# Tasmota_ESP32C6-2.net
KiCad netlist of a schematic drawn in EAGLE
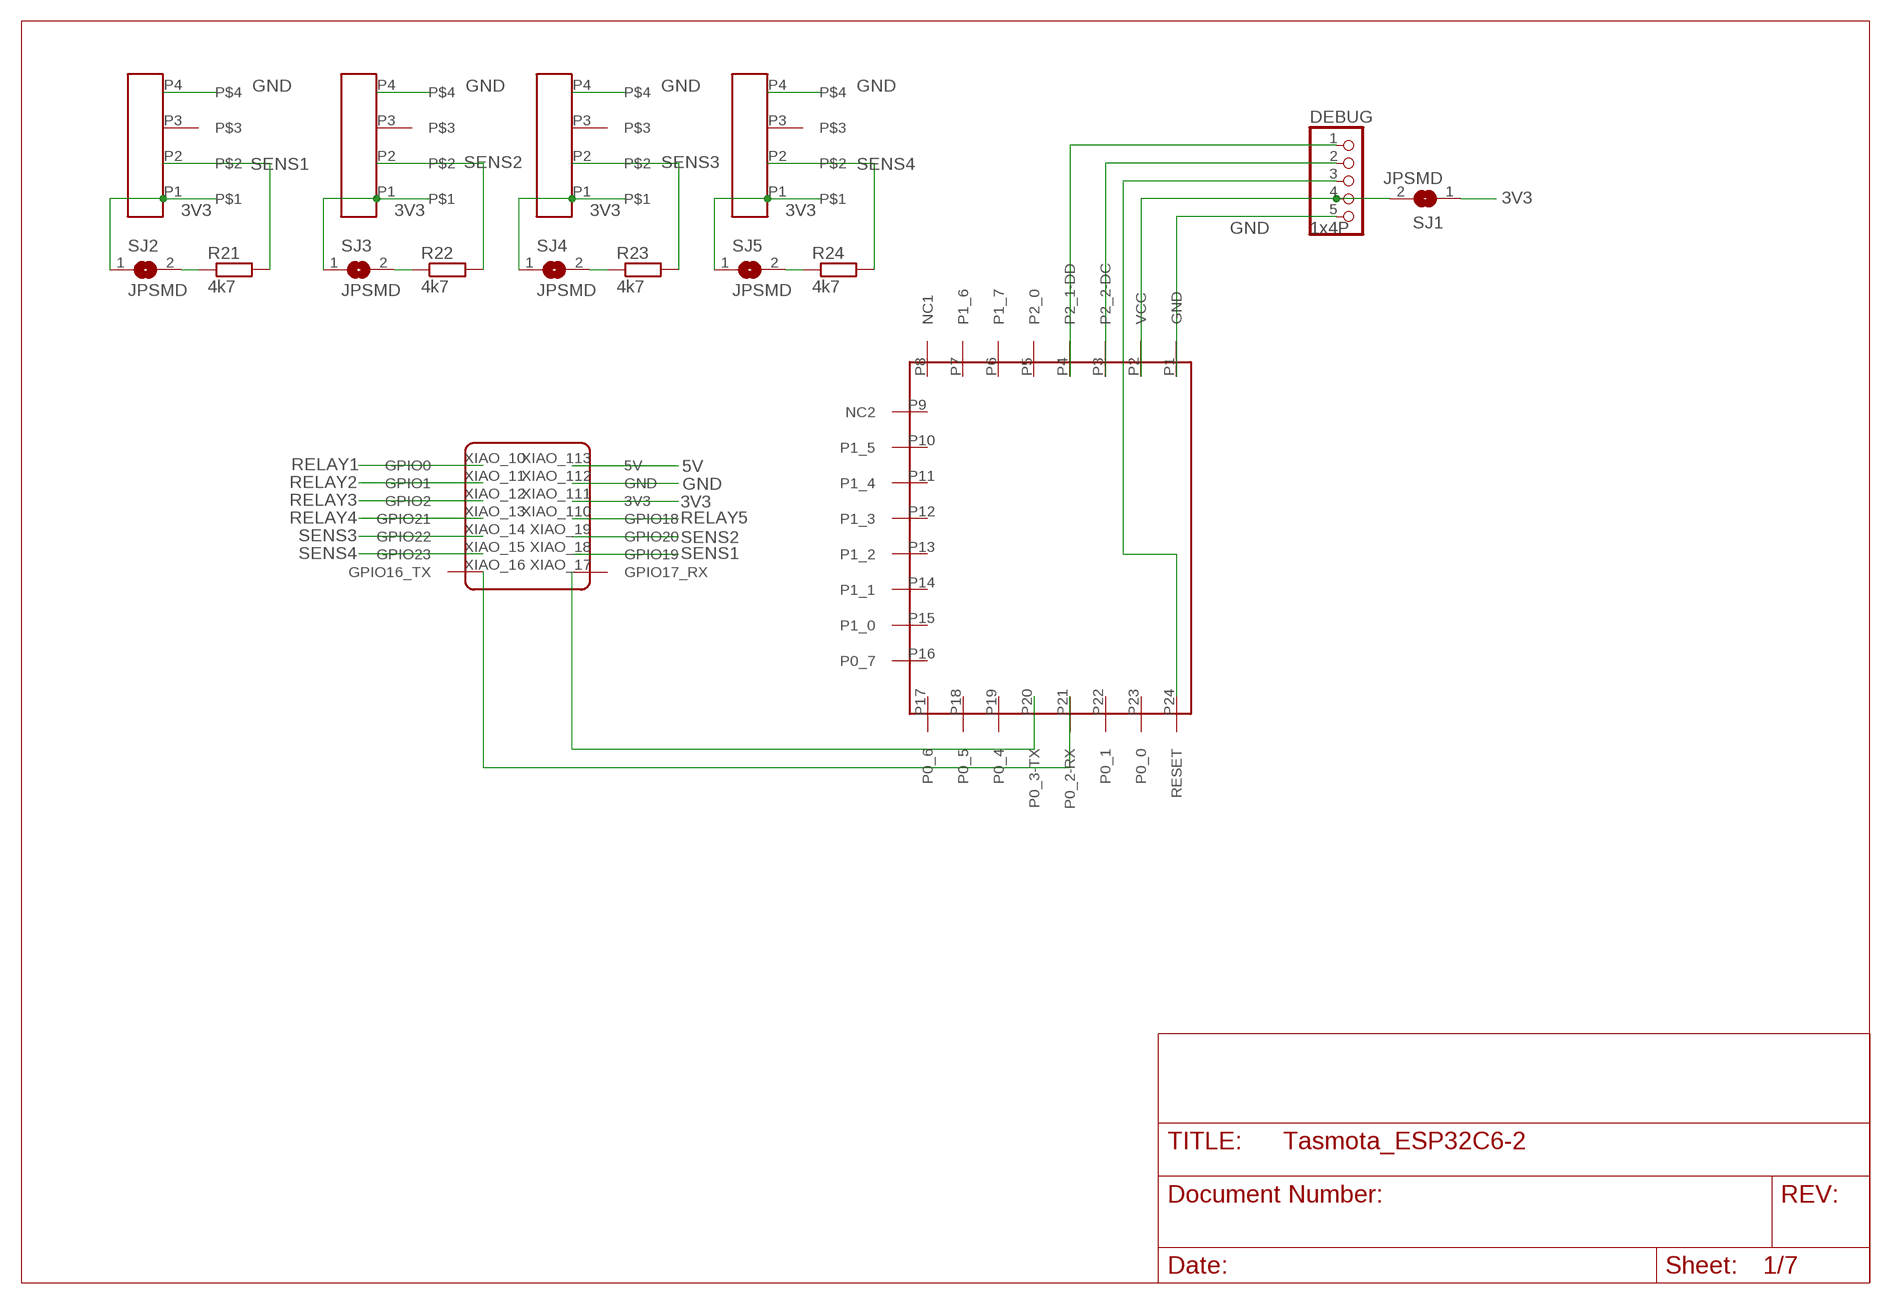
[diagram p0: schematic, sheet 1]
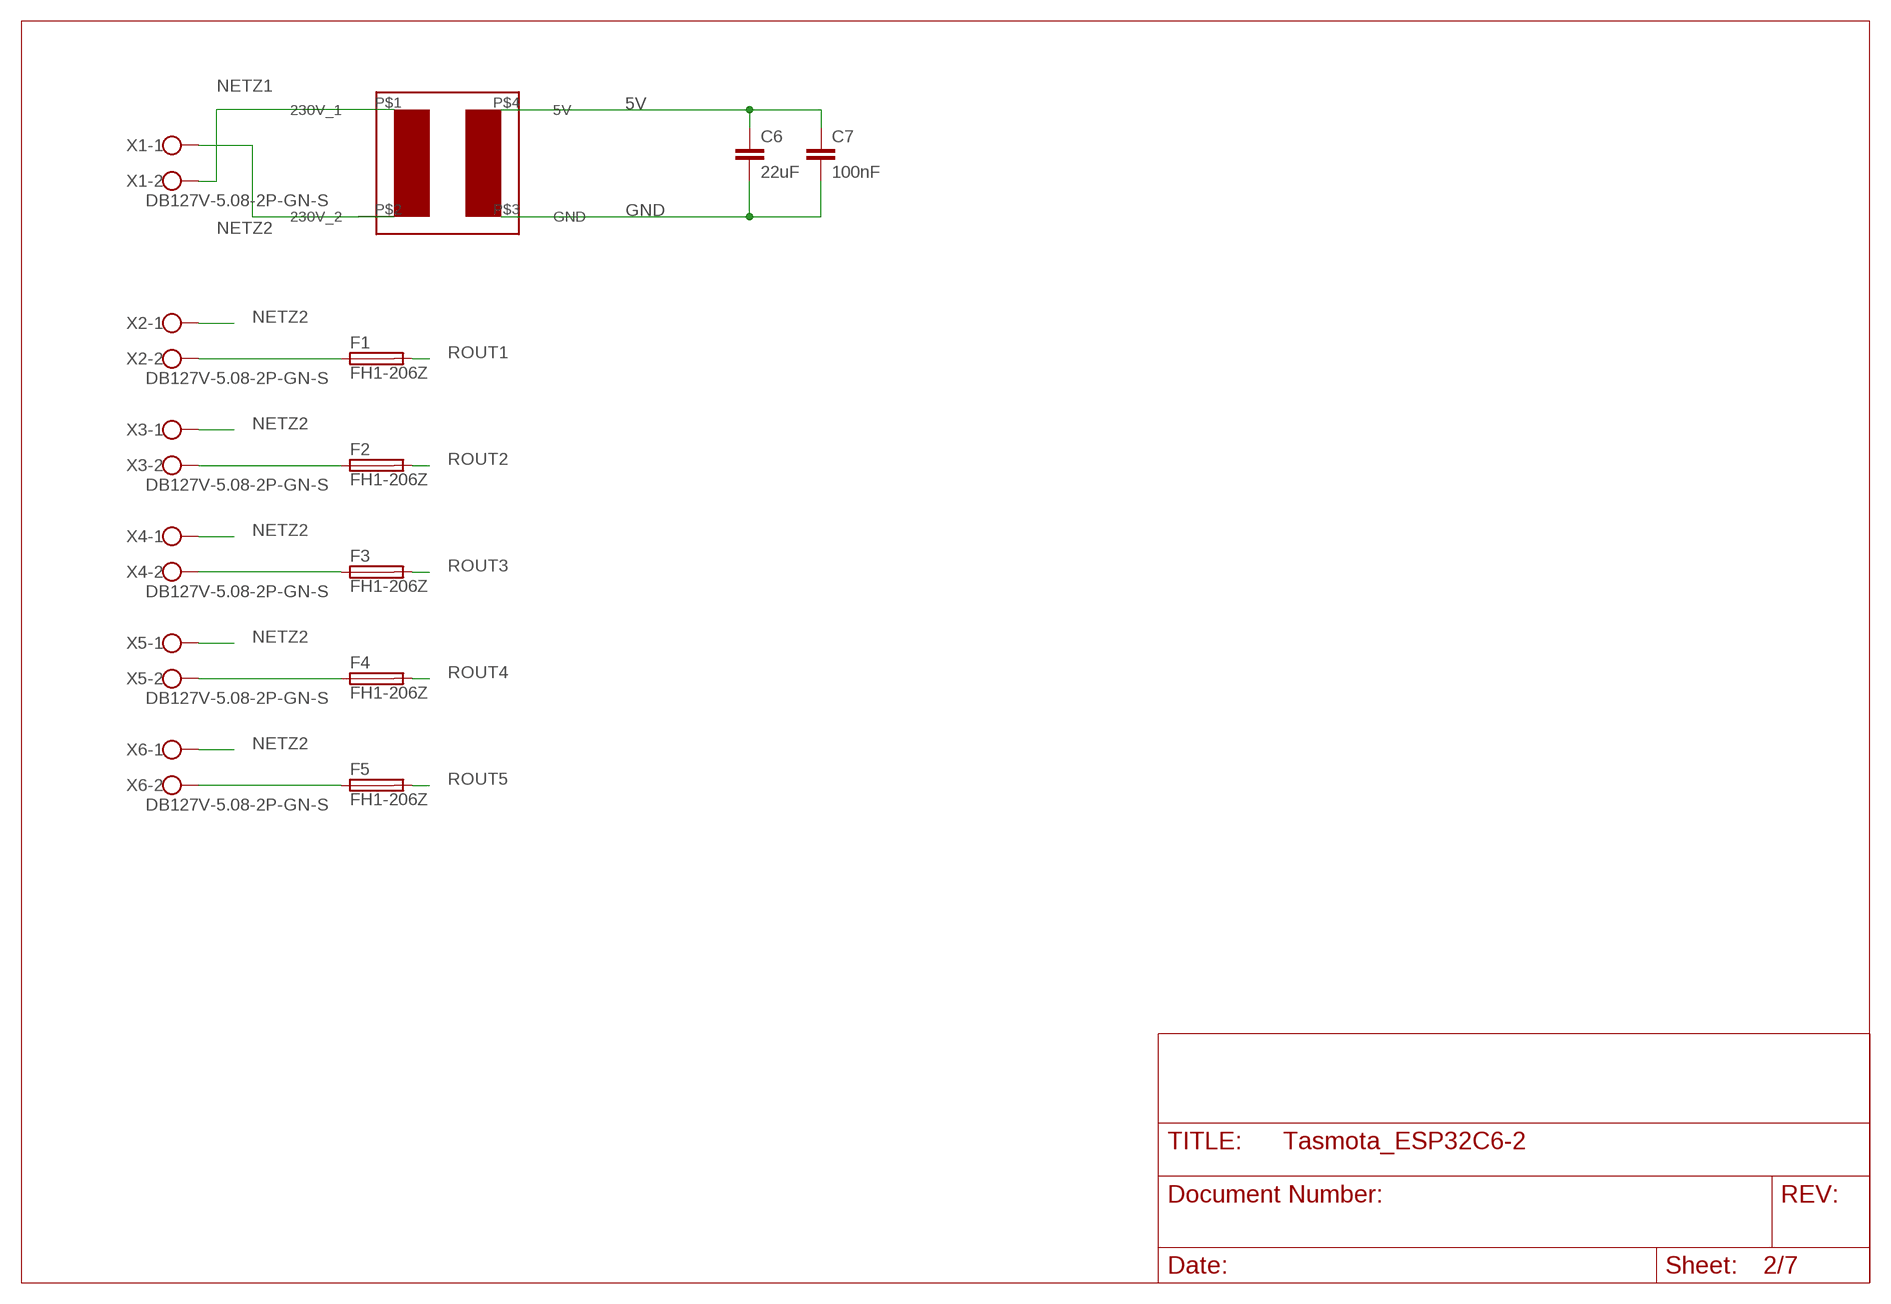
[diagram p1: schematic, sheet 2]
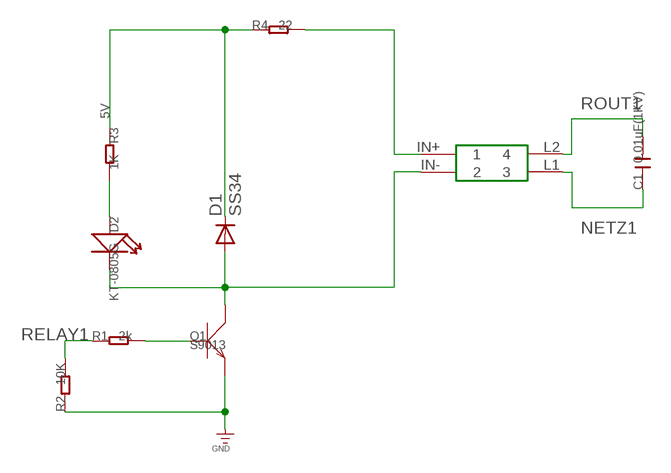
[diagram p2: schematic, sheet 3]
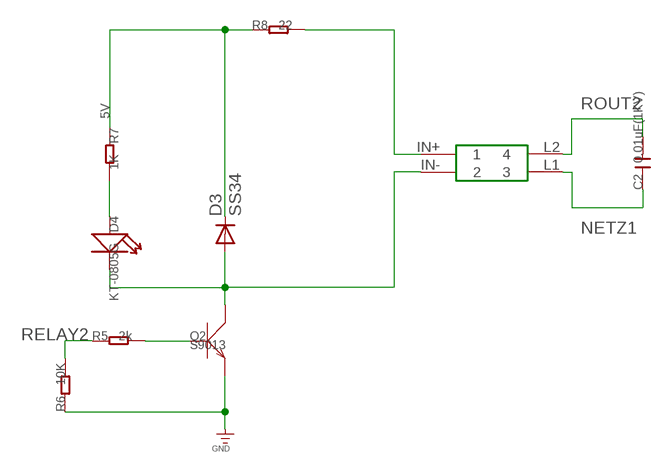
[diagram p3: schematic, sheet 4]
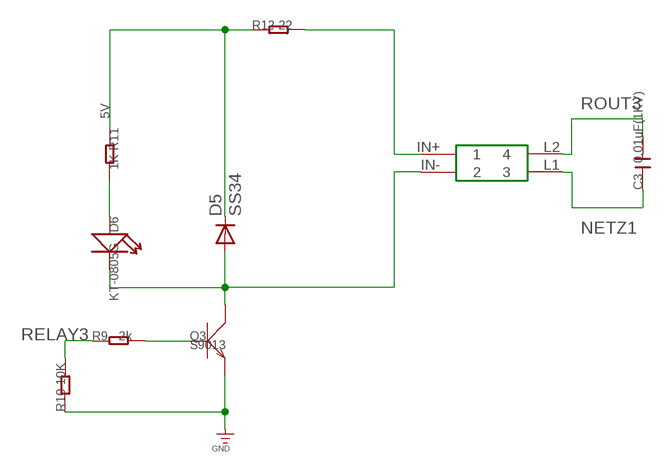
[diagram p4: schematic, sheet 5]
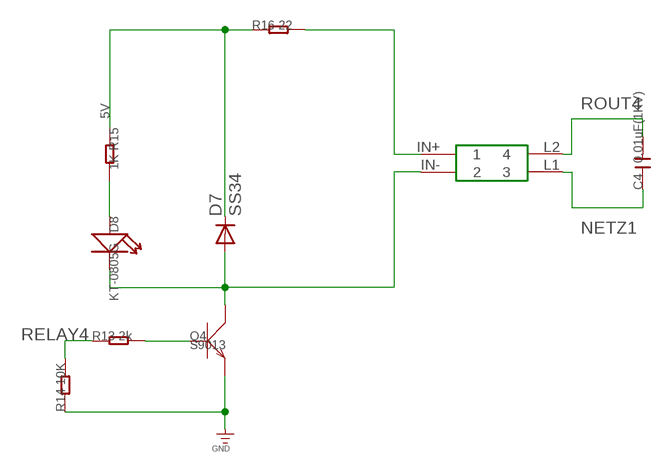
[diagram p5: schematic, sheet 6]
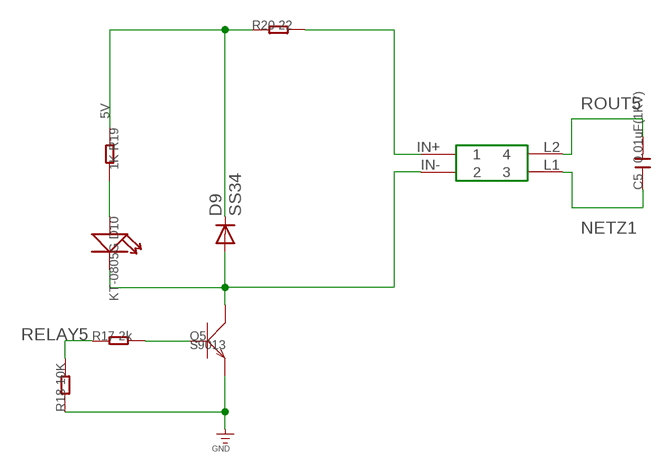
[diagram p6: schematic, sheet 7]

(export (version "E")
  (design (tool "Eeschema 10.0.6"))
  (components
    (comp (ref "C1")
      (value "0.01uF(1KV)")
      (footprint "eagle-import:C1206")
      (libsource (lib "eagle-import") (part "C-1206"))
    )
    (comp (ref "D1")
      (value "SS34")
      (footprint "eagle-import:DO-214AC")
      (libsource (lib "eagle-import") (part "DIODE-DO-214AC"))
    )
    (comp (ref "D2")
      (value "KT-0805G")
      (footprint "eagle-import:LED-0805")
      (libsource (lib "eagle-import") (part "LED'0805'"))
    )
    (comp (ref "Q1")
      (value "S9013")
      (footprint "eagle-import:SOT23")
      (libsource (lib "eagle-import") (part "TRANSISTOR-NPN-SOT23"))
    )
    (comp (ref "R1")
      (value "2k")
      (footprint "eagle-import:R0805")
      (libsource (lib "eagle-import") (part "R-0805"))
    )
    (comp (ref "R2")
      (value "10K")
      (footprint "eagle-import:R0805")
      (libsource (lib "eagle-import") (part "R-0805"))
    )
    (comp (ref "R3")
      (value "1K")
      (footprint "eagle-import:R0805")
      (libsource (lib "eagle-import") (part "R-0805"))
    )
    (comp (ref "R4")
      (value "22")
      (footprint "eagle-import:R0805")
      (libsource (lib "eagle-import") (part "R-0805"))
    )
    (comp (ref "U$4")
      (value "G3MB-202P")
      (footprint "eagle-import:G3MB-202(RELAY)")
      (libsource (lib "eagle-import") (part "G3MB-202(RELAY)"))
    )
    (comp (ref "DEBUG")
      (value "1x4P")
      (footprint "eagle-import:1X05")
      (libsource (lib "eagle-import") (part "PINHD-1X5"))
    )
    (comp (ref "R21")
      (value "4k7")
      (footprint "eagle-import:R0805")
      (libsource (lib "eagle-import") (part "R-EU_R0805"))
    )
    (comp (ref "R22")
      (value "4k7")
      (footprint "eagle-import:R0805")
      (libsource (lib "eagle-import") (part "R-EU_R0805"))
    )
    (comp (ref "R23")
      (value "4k7")
      (footprint "eagle-import:R0805")
      (libsource (lib "eagle-import") (part "R-EU_R0805"))
    )
    (comp (ref "R24")
      (value "4k7")
      (footprint "eagle-import:R0805")
      (libsource (lib "eagle-import") (part "R-EU_R0805"))
    )
    (comp (ref "SENSOR1")
      (value "GMX-N-44")
      (footprint "eagle-import:GMX-N-4")
      (libsource (lib "eagle-import") (part "GMX-N-4"))
    )
    (comp (ref "SENSOR2")
      (value "GMX-N-44")
      (footprint "eagle-import:GMX-N-4")
      (libsource (lib "eagle-import") (part "GMX-N-4"))
    )
    (comp (ref "SENSOR3")
      (value "GMX-N-44")
      (footprint "eagle-import:GMX-N-4")
      (libsource (lib "eagle-import") (part "GMX-N-4"))
    )
    (comp (ref "SENSOR4")
      (value "GMX-N-44")
      (footprint "eagle-import:GMX-N-4")
      (libsource (lib "eagle-import") (part "GMX-N-4"))
    )
    (comp (ref "SJ1")
      (value "JPSMD")
      (footprint "eagle-import:SJ")
      (libsource (lib "eagle-import") (part "SJ"))
    )
    (comp (ref "SJ2")
      (value "JPSMD")
      (footprint "eagle-import:SJ")
      (libsource (lib "eagle-import") (part "SJ"))
    )
    (comp (ref "SJ3")
      (value "JPSMD")
      (footprint "eagle-import:SJ")
      (libsource (lib "eagle-import") (part "SJ"))
    )
    (comp (ref "SJ4")
      (value "JPSMD")
      (footprint "eagle-import:SJ")
      (libsource (lib "eagle-import") (part "SJ"))
    )
    (comp (ref "SJ5")
      (value "JPSMD")
      (footprint "eagle-import:SJ")
      (libsource (lib "eagle-import") (part "SJ"))
    )
    (comp (ref "U$1")
      (value "1x7P")
      (footprint "eagle-import:XIAO_ESP32C6")
      (libsource (lib "eagle-import") (part "XIAO_ESP32C6"))
    )
    (comp (ref "U$2")
      (value "EBYTE-E18-MS1")
      (footprint "eagle-import:EBYTE-E18-MS1")
      (libsource (lib "eagle-import") (part "EBYTE-E18-MS1"))
    )
    (comp (ref "C3")
      (value "0.01uF(1KV)")
      (footprint "eagle-import:C1206")
      (libsource (lib "eagle-import") (part "C-1206"))
    )
    (comp (ref "D5")
      (value "SS34")
      (footprint "eagle-import:DO-214AC")
      (libsource (lib "eagle-import") (part "DIODE-DO-214AC"))
    )
    (comp (ref "D6")
      (value "KT-0805G")
      (footprint "eagle-import:LED-0805")
      (libsource (lib "eagle-import") (part "LED'0805'"))
    )
    (comp (ref "Q3")
      (value "S9013")
      (footprint "eagle-import:SOT23")
      (libsource (lib "eagle-import") (part "TRANSISTOR-NPN-SOT23"))
    )
    (comp (ref "R9")
      (value "2k")
      (footprint "eagle-import:R0805")
      (libsource (lib "eagle-import") (part "R-0805"))
    )
    (comp (ref "R10")
      (value "10K")
      (footprint "eagle-import:R0805")
      (libsource (lib "eagle-import") (part "R-0805"))
    )
    (comp (ref "R11")
      (value "1K")
      (footprint "eagle-import:R0805")
      (libsource (lib "eagle-import") (part "R-0805"))
    )
    (comp (ref "R12")
      (value "22")
      (footprint "eagle-import:R0805")
      (libsource (lib "eagle-import") (part "R-0805"))
    )
    (comp (ref "U$8")
      (value "G3MB-202P")
      (footprint "eagle-import:G3MB-202(RELAY)")
      (libsource (lib "eagle-import") (part "G3MB-202(RELAY)"))
    )
    (comp (ref "C4")
      (value "0.01uF(1KV)")
      (footprint "eagle-import:C1206")
      (libsource (lib "eagle-import") (part "C-1206"))
    )
    (comp (ref "D7")
      (value "SS34")
      (footprint "eagle-import:DO-214AC")
      (libsource (lib "eagle-import") (part "DIODE-DO-214AC"))
    )
    (comp (ref "D8")
      (value "KT-0805G")
      (footprint "eagle-import:LED-0805")
      (libsource (lib "eagle-import") (part "LED'0805'"))
    )
    (comp (ref "Q4")
      (value "S9013")
      (footprint "eagle-import:SOT23")
      (libsource (lib "eagle-import") (part "TRANSISTOR-NPN-SOT23"))
    )
    (comp (ref "R13")
      (value "2k")
      (footprint "eagle-import:R0805")
      (libsource (lib "eagle-import") (part "R-0805"))
    )
    (comp (ref "R14")
      (value "10K")
      (footprint "eagle-import:R0805")
      (libsource (lib "eagle-import") (part "R-0805"))
    )
    (comp (ref "R15")
      (value "1K")
      (footprint "eagle-import:R0805")
      (libsource (lib "eagle-import") (part "R-0805"))
    )
    (comp (ref "R16")
      (value "22")
      (footprint "eagle-import:R0805")
      (libsource (lib "eagle-import") (part "R-0805"))
    )
    (comp (ref "U$10")
      (value "G3MB-202P")
      (footprint "eagle-import:G3MB-202(RELAY)")
      (libsource (lib "eagle-import") (part "G3MB-202(RELAY)"))
    )
    (comp (ref "C6")
      (value "22uF")
      (footprint "eagle-import:C0805")
      (libsource (lib "eagle-import") (part "C-EUC0805"))
    )
    (comp (ref "C7")
      (value "100nF")
      (footprint "eagle-import:C0805")
      (libsource (lib "eagle-import") (part "C-EUC0805"))
    )
    (comp (ref "F1")
      (value "FH1-206Z")
      (footprint "eagle-import:FUSEHOLDER_10")
      (libsource (lib "eagle-import") (part "FUSEHOLDER_10"))
    )
    (comp (ref "F2")
      (value "FH1-206Z")
      (footprint "eagle-import:FUSEHOLDER_10")
      (libsource (lib "eagle-import") (part "FUSEHOLDER_10"))
    )
    (comp (ref "F3")
      (value "FH1-206Z")
      (footprint "eagle-import:FUSEHOLDER_10")
      (libsource (lib "eagle-import") (part "FUSEHOLDER_10"))
    )
    (comp (ref "F4")
      (value "FH1-206Z")
      (footprint "eagle-import:FUSEHOLDER_10")
      (libsource (lib "eagle-import") (part "FUSEHOLDER_10"))
    )
    (comp (ref "F5")
      (value "FH1-206Z")
      (footprint "eagle-import:FUSEHOLDER_10")
      (libsource (lib "eagle-import") (part "FUSEHOLDER_10"))
    )
    (comp (ref "U$3")
      (value "HAW3-220S05T2")
      (footprint "eagle-import:HAW3-220S05T2")
      (libsource (lib "eagle-import") (part "HAW3-220S05T2"))
    )
    (comp (ref "X1")
      (value "DB127V-5.08-2P-GN-S")
      (footprint "eagle-import:W237-102")
      (fields (field (name "MPN") "237-102"))
      (libsource (lib "eagle-import") (part "con-wago-500_195_W237-102"))
    )
    (comp (ref "X2")
      (value "DB127V-5.08-2P-GN-S")
      (footprint "eagle-import:W237-102")
      (fields (field (name "MPN") "237-102"))
      (libsource (lib "eagle-import") (part "W237-102"))
    )
    (comp (ref "X3")
      (value "DB127V-5.08-2P-GN-S")
      (footprint "eagle-import:W237-102")
      (fields (field (name "MPN") "237-102"))
      (libsource (lib "eagle-import") (part "W237-102"))
    )
    (comp (ref "X4")
      (value "DB127V-5.08-2P-GN-S")
      (footprint "eagle-import:W237-102")
      (fields (field (name "MPN") "237-102"))
      (libsource (lib "eagle-import") (part "W237-102"))
    )
    (comp (ref "X5")
      (value "DB127V-5.08-2P-GN-S")
      (footprint "eagle-import:W237-102")
      (fields (field (name "MPN") "237-102"))
      (libsource (lib "eagle-import") (part "W237-102"))
    )
    (comp (ref "X6")
      (value "DB127V-5.08-2P-GN-S")
      (footprint "eagle-import:W237-102")
      (fields (field (name "MPN") "237-102"))
      (libsource (lib "eagle-import") (part "W237-102"))
    )
    (comp (ref "C2")
      (value "0.01uF(1KV)")
      (footprint "eagle-import:C1206")
      (libsource (lib "eagle-import") (part "C-1206"))
    )
    (comp (ref "D3")
      (value "SS34")
      (footprint "eagle-import:DO-214AC")
      (libsource (lib "eagle-import") (part "DIODE-DO-214AC"))
    )
    (comp (ref "D4")
      (value "KT-0805G")
      (footprint "eagle-import:LED-0805")
      (libsource (lib "eagle-import") (part "LED'0805'"))
    )
    (comp (ref "Q2")
      (value "S9013")
      (footprint "eagle-import:SOT23")
      (libsource (lib "eagle-import") (part "TRANSISTOR-NPN-SOT23"))
    )
    (comp (ref "R5")
      (value "2k")
      (footprint "eagle-import:R0805")
      (libsource (lib "eagle-import") (part "R-0805"))
    )
    (comp (ref "R6")
      (value "10K")
      (footprint "eagle-import:R0805")
      (libsource (lib "eagle-import") (part "R-0805"))
    )
    (comp (ref "R7")
      (value "1K")
      (footprint "eagle-import:R0805")
      (libsource (lib "eagle-import") (part "R-0805"))
    )
    (comp (ref "R8")
      (value "22")
      (footprint "eagle-import:R0805")
      (libsource (lib "eagle-import") (part "R-0805"))
    )
    (comp (ref "U$6")
      (value "G3MB-202P")
      (footprint "eagle-import:G3MB-202(RELAY)")
      (libsource (lib "eagle-import") (part "G3MB-202(RELAY)"))
    )
    (comp (ref "C5")
      (value "0.01uF(1KV)")
      (footprint "eagle-import:C1206")
      (libsource (lib "eagle-import") (part "C-1206"))
    )
    (comp (ref "D9")
      (value "SS34")
      (footprint "eagle-import:DO-214AC")
      (libsource (lib "eagle-import") (part "DIODE-DO-214AC"))
    )
    (comp (ref "D10")
      (value "KT-0805G")
      (footprint "eagle-import:LED-0805")
      (libsource (lib "eagle-import") (part "LED'0805'"))
    )
    (comp (ref "Q5")
      (value "S9013")
      (footprint "eagle-import:SOT23")
      (libsource (lib "eagle-import") (part "TRANSISTOR-NPN-SOT23"))
    )
    (comp (ref "R17")
      (value "2k")
      (footprint "eagle-import:R0805")
      (libsource (lib "eagle-import") (part "R-0805"))
    )
    (comp (ref "R18")
      (value "10K")
      (footprint "eagle-import:R0805")
      (libsource (lib "eagle-import") (part "R-0805"))
    )
    (comp (ref "R19")
      (value "1K")
      (footprint "eagle-import:R0805")
      (libsource (lib "eagle-import") (part "R-0805"))
    )
    (comp (ref "R20")
      (value "22")
      (footprint "eagle-import:R0805")
      (libsource (lib "eagle-import") (part "R-0805"))
    )
    (comp (ref "U$12")
      (value "G3MB-202P")
      (footprint "eagle-import:G3MB-202(RELAY)")
      (libsource (lib "eagle-import") (part "G3MB-202(RELAY)"))
    )
  )
  (nets
    (net (code "1") (name "3V3") (class "Default")
      (node (ref "SENSOR1") (pin "P1") (pinfunction "P$1_P1") (pintype "bidirectional"))
      (node (ref "SENSOR2") (pin "P1") (pinfunction "P$1_P1") (pintype "bidirectional"))
      (node (ref "SENSOR3") (pin "P1") (pinfunction "P$1_P1") (pintype "bidirectional"))
      (node (ref "SENSOR4") (pin "P1") (pinfunction "P$1_P1") (pintype "bidirectional"))
      (node (ref "SJ1") (pin "1") (pinfunction "1_1") (pintype "passive"))
      (node (ref "SJ2") (pin "1") (pinfunction "1_1") (pintype "passive"))
      (node (ref "SJ3") (pin "1") (pinfunction "1_1") (pintype "passive"))
      (node (ref "SJ4") (pin "1") (pinfunction "1_1") (pintype "passive"))
      (node (ref "SJ5") (pin "1") (pinfunction "1_1") (pintype "passive"))
      (node (ref "U$1") (pin "XIAO_111") (pinfunction "3V3_XIAO_111") (pintype "power_in"))
    )
    (net (code "2") (name "5V") (class "Default")
      (node (ref "C6") (pin "1") (pinfunction "1_1") (pintype "passive"))
      (node (ref "C7") (pin "1") (pinfunction "1_1") (pintype "passive"))
      (node (ref "D1") (pin "C") (pinfunction "C_C") (pintype "passive"))
      (node (ref "D3") (pin "C") (pinfunction "C_C") (pintype "passive"))
      (node (ref "D5") (pin "C") (pinfunction "C_C") (pintype "passive"))
      (node (ref "D7") (pin "C") (pinfunction "C_C") (pintype "passive"))
      (node (ref "D9") (pin "C") (pinfunction "C_C") (pintype "passive"))
      (node (ref "R11") (pin "1") (pinfunction "1_1") (pintype "passive"))
      (node (ref "R12") (pin "1") (pinfunction "1_1") (pintype "passive"))
      (node (ref "R15") (pin "1") (pinfunction "1_1") (pintype "passive"))
      (node (ref "R16") (pin "1") (pinfunction "1_1") (pintype "passive"))
      (node (ref "R19") (pin "1") (pinfunction "1_1") (pintype "passive"))
      (node (ref "R20") (pin "1") (pinfunction "1_1") (pintype "passive"))
      (node (ref "R3") (pin "1") (pinfunction "1_1") (pintype "passive"))
      (node (ref "R4") (pin "1") (pinfunction "1_1") (pintype "passive"))
      (node (ref "R7") (pin "1") (pinfunction "1_1") (pintype "passive"))
      (node (ref "R8") (pin "1") (pinfunction "1_1") (pintype "passive"))
      (node (ref "U$1") (pin "XIAO_113") (pinfunction "5V_XIAO_113") (pintype "power_in"))
      (node (ref "U$3") (pin "P$4") (pinfunction "5V_P$4") (pintype "bidirectional"))
    )
    (net (code "3") (name "GND") (class "Default")
      (node (ref "C6") (pin "2") (pinfunction "2_2") (pintype "passive"))
      (node (ref "C7") (pin "2") (pinfunction "2_2") (pintype "passive"))
      (node (ref "DEBUG") (pin "5") (pinfunction "5_5") (pintype "passive"))
      (node (ref "Q1") (pin "2") (pinfunction "E_2") (pintype "passive"))
      (node (ref "Q2") (pin "2") (pinfunction "E_2") (pintype "passive"))
      (node (ref "Q3") (pin "2") (pinfunction "E_2") (pintype "passive"))
      (node (ref "Q4") (pin "2") (pinfunction "E_2") (pintype "passive"))
      (node (ref "Q5") (pin "2") (pinfunction "E_2") (pintype "passive"))
      (node (ref "R10") (pin "1") (pinfunction "1_1") (pintype "passive"))
      (node (ref "R14") (pin "1") (pinfunction "1_1") (pintype "passive"))
      (node (ref "R18") (pin "1") (pinfunction "1_1") (pintype "passive"))
      (node (ref "R2") (pin "1") (pinfunction "1_1") (pintype "passive"))
      (node (ref "R6") (pin "1") (pinfunction "1_1") (pintype "passive"))
      (node (ref "SENSOR1") (pin "P4") (pinfunction "P$4_P4") (pintype "bidirectional"))
      (node (ref "SENSOR2") (pin "P4") (pinfunction "P$4_P4") (pintype "bidirectional"))
      (node (ref "SENSOR3") (pin "P4") (pinfunction "P$4_P4") (pintype "bidirectional"))
      (node (ref "SENSOR4") (pin "P4") (pinfunction "P$4_P4") (pintype "bidirectional"))
      (node (ref "U$1") (pin "XIAO_112") (pinfunction "GND_XIAO_112") (pintype "power_in"))
      (node (ref "U$2") (pin "P1") (pinfunction "GND_P1") (pintype "power_in"))
      (node (ref "U$3") (pin "P$3") (pinfunction "GND_P$3") (pintype "bidirectional"))
    )
    (net (code "4") (name "NETZ1") (class "Default")
      (node (ref "C1") (pin "1") (pinfunction "1_1") (pintype "passive"))
      (node (ref "C2") (pin "1") (pinfunction "1_1") (pintype "passive"))
      (node (ref "C3") (pin "1") (pinfunction "1_1") (pintype "passive"))
      (node (ref "C4") (pin "1") (pinfunction "1_1") (pintype "passive"))
      (node (ref "C5") (pin "1") (pinfunction "1_1") (pintype "passive"))
      (node (ref "U$10") (pin "L1") (pinfunction "3_L1") (pintype "bidirectional"))
      (node (ref "U$12") (pin "L1") (pinfunction "3_L1") (pintype "bidirectional"))
      (node (ref "U$3") (pin "P$1") (pinfunction "230V_1_P$1") (pintype "bidirectional"))
      (node (ref "U$4") (pin "L1") (pinfunction "3_L1") (pintype "bidirectional"))
      (node (ref "U$6") (pin "L1") (pinfunction "3_L1") (pintype "bidirectional"))
      (node (ref "U$8") (pin "L1") (pinfunction "3_L1") (pintype "bidirectional"))
      (node (ref "X1") (pin "2") (pinfunction "KL_2") (pintype "passive"))
    )
    (net (code "5") (name "NETZ2") (class "Default")
      (node (ref "U$3") (pin "P$2") (pinfunction "230V_2_P$2") (pintype "bidirectional"))
      (node (ref "X1") (pin "1") (pinfunction "KL_1") (pintype "passive"))
      (node (ref "X2") (pin "1") (pinfunction "KL_1") (pintype "passive"))
      (node (ref "X3") (pin "1") (pinfunction "KL_1") (pintype "passive"))
      (node (ref "X4") (pin "1") (pinfunction "KL_1") (pintype "passive"))
      (node (ref "X5") (pin "1") (pinfunction "KL_1") (pintype "passive"))
      (node (ref "X6") (pin "1") (pinfunction "KL_1") (pintype "passive"))
    )
    (net (code "6") (name "Net-(D2-Pad+)") (class "Default")
      (node (ref "D2") (pin "+") (pinfunction "+_+") (pintype "passive"))
      (node (ref "R3") (pin "2") (pinfunction "2_2") (pintype "passive"))
    )
    (net (code "7") (name "Net-(D4-Pad+)") (class "Default")
      (node (ref "D4") (pin "+") (pinfunction "+_+") (pintype "passive"))
      (node (ref "R7") (pin "2") (pinfunction "2_2") (pintype "passive"))
    )
    (net (code "8") (name "Net-(D6-Pad+)") (class "Default")
      (node (ref "D6") (pin "+") (pinfunction "+_+") (pintype "passive"))
      (node (ref "R11") (pin "2") (pinfunction "2_2") (pintype "passive"))
    )
    (net (code "9") (name "Net-(D8-Pad+)") (class "Default")
      (node (ref "D8") (pin "+") (pinfunction "+_+") (pintype "passive"))
      (node (ref "R15") (pin "2") (pinfunction "2_2") (pintype "passive"))
    )
    (net (code "10") (name "Net-(D10-Pad+)") (class "Default")
      (node (ref "D10") (pin "+") (pinfunction "+_+") (pintype "passive"))
      (node (ref "R19") (pin "2") (pinfunction "2_2") (pintype "passive"))
    )
    (net (code "11") (name "Net-(Q1-B)") (class "Default")
      (node (ref "Q1") (pin "1") (pinfunction "B_1") (pintype "passive"))
      (node (ref "R1") (pin "2") (pinfunction "2_2") (pintype "passive"))
    )
    (net (code "12") (name "Net-(Q1-C)") (class "Default")
      (node (ref "D1") (pin "A") (pinfunction "A_A") (pintype "passive"))
      (node (ref "D2") (pin "-") (pinfunction "-_-") (pintype "passive"))
      (node (ref "Q1") (pin "3") (pinfunction "C_3") (pintype "passive"))
      (node (ref "U$4") (pin "IN-") (pinfunction "2_IN-") (pintype "bidirectional"))
    )
    (net (code "13") (name "Net-(Q2-B)") (class "Default")
      (node (ref "Q2") (pin "1") (pinfunction "B_1") (pintype "passive"))
      (node (ref "R5") (pin "2") (pinfunction "2_2") (pintype "passive"))
    )
    (net (code "14") (name "Net-(Q2-C)") (class "Default")
      (node (ref "D3") (pin "A") (pinfunction "A_A") (pintype "passive"))
      (node (ref "D4") (pin "-") (pinfunction "-_-") (pintype "passive"))
      (node (ref "Q2") (pin "3") (pinfunction "C_3") (pintype "passive"))
      (node (ref "U$6") (pin "IN-") (pinfunction "2_IN-") (pintype "bidirectional"))
    )
    (net (code "15") (name "Net-(Q3-B)") (class "Default")
      (node (ref "Q3") (pin "1") (pinfunction "B_1") (pintype "passive"))
      (node (ref "R9") (pin "2") (pinfunction "2_2") (pintype "passive"))
    )
    (net (code "16") (name "Net-(Q3-C)") (class "Default")
      (node (ref "D5") (pin "A") (pinfunction "A_A") (pintype "passive"))
      (node (ref "D6") (pin "-") (pinfunction "-_-") (pintype "passive"))
      (node (ref "Q3") (pin "3") (pinfunction "C_3") (pintype "passive"))
      (node (ref "U$8") (pin "IN-") (pinfunction "2_IN-") (pintype "bidirectional"))
    )
    (net (code "17") (name "Net-(Q4-B)") (class "Default")
      (node (ref "Q4") (pin "1") (pinfunction "B_1") (pintype "passive"))
      (node (ref "R13") (pin "2") (pinfunction "2_2") (pintype "passive"))
    )
    (net (code "18") (name "Net-(Q4-C)") (class "Default")
      (node (ref "D7") (pin "A") (pinfunction "A_A") (pintype "passive"))
      (node (ref "D8") (pin "-") (pinfunction "-_-") (pintype "passive"))
      (node (ref "Q4") (pin "3") (pinfunction "C_3") (pintype "passive"))
      (node (ref "U$10") (pin "IN-") (pinfunction "2_IN-") (pintype "bidirectional"))
    )
    (net (code "19") (name "Net-(Q5-B)") (class "Default")
      (node (ref "Q5") (pin "1") (pinfunction "B_1") (pintype "passive"))
      (node (ref "R17") (pin "2") (pinfunction "2_2") (pintype "passive"))
    )
    (net (code "20") (name "Net-(Q5-C)") (class "Default")
      (node (ref "D10") (pin "-") (pinfunction "-_-") (pintype "passive"))
      (node (ref "D9") (pin "A") (pinfunction "A_A") (pintype "passive"))
      (node (ref "Q5") (pin "3") (pinfunction "C_3") (pintype "passive"))
      (node (ref "U$12") (pin "IN-") (pinfunction "2_IN-") (pintype "bidirectional"))
    )
    (net (code "21") (name "Net-(R21-Pad1)") (class "Default")
      (node (ref "R21") (pin "1") (pinfunction "1_1") (pintype "passive"))
      (node (ref "SJ2") (pin "2") (pinfunction "2_2") (pintype "passive"))
    )
    (net (code "22") (name "Net-(R22-Pad1)") (class "Default")
      (node (ref "R22") (pin "1") (pinfunction "1_1") (pintype "passive"))
      (node (ref "SJ3") (pin "2") (pinfunction "2_2") (pintype "passive"))
    )
    (net (code "23") (name "Net-(R23-Pad1)") (class "Default")
      (node (ref "R23") (pin "1") (pinfunction "1_1") (pintype "passive"))
      (node (ref "SJ4") (pin "2") (pinfunction "2_2") (pintype "passive"))
    )
    (net (code "24") (name "Net-(R24-Pad1)") (class "Default")
      (node (ref "R24") (pin "1") (pinfunction "1_1") (pintype "passive"))
      (node (ref "SJ5") (pin "2") (pinfunction "2_2") (pintype "passive"))
    )
    (net (code "25") (name "Net-(U$1-GPIO16_TX)") (class "Default")
      (node (ref "U$1") (pin "XIAO_16") (pinfunction "GPIO16_TX_XIAO_16") (pintype "bidirectional"))
      (node (ref "U$2") (pin "P21") (pinfunction "P0_2-RX_P21") (pintype "bidirectional"))
    )
    (net (code "26") (name "Net-(U$1-GPIO17_RX)") (class "Default")
      (node (ref "U$1") (pin "XIAO_17") (pinfunction "GPIO17_RX_XIAO_17") (pintype "bidirectional"))
      (node (ref "U$2") (pin "P20") (pinfunction "P0_3-TX_P20") (pintype "bidirectional"))
    )
    (net (code "27") (name "Net-(U$2-P2_1-DD)") (class "Default")
      (node (ref "DEBUG") (pin "1") (pinfunction "1_1") (pintype "passive"))
      (node (ref "U$2") (pin "P4") (pinfunction "P2_1-DD_P4") (pintype "bidirectional"))
    )
    (net (code "28") (name "Net-(U$2-P2_2-DC)") (class "Default")
      (node (ref "DEBUG") (pin "2") (pinfunction "2_2") (pintype "passive"))
      (node (ref "U$2") (pin "P3") (pinfunction "P2_2-DC_P3") (pintype "bidirectional"))
    )
    (net (code "29") (name "Net-(U$2-RESET)") (class "Default")
      (node (ref "DEBUG") (pin "3") (pinfunction "3_3") (pintype "passive"))
      (node (ref "U$2") (pin "P24") (pinfunction "RESET_P24") (pintype "bidirectional"))
    )
    (net (code "30") (name "Net-(U$2-VCC)") (class "Default")
      (node (ref "DEBUG") (pin "4") (pinfunction "4_4") (pintype "passive"))
      (node (ref "SJ1") (pin "2") (pinfunction "2_2") (pintype "passive"))
      (node (ref "U$2") (pin "P2") (pinfunction "VCC_P2") (pintype "power_in"))
    )
    (net (code "31") (name "Net-(U$4-1)") (class "Default")
      (node (ref "R4") (pin "2") (pinfunction "2_2") (pintype "passive"))
      (node (ref "U$4") (pin "IN+") (pinfunction "1_IN+") (pintype "bidirectional"))
    )
    (net (code "32") (name "Net-(U$6-1)") (class "Default")
      (node (ref "R8") (pin "2") (pinfunction "2_2") (pintype "passive"))
      (node (ref "U$6") (pin "IN+") (pinfunction "1_IN+") (pintype "bidirectional"))
    )
    (net (code "33") (name "Net-(U$8-1)") (class "Default")
      (node (ref "R12") (pin "2") (pinfunction "2_2") (pintype "passive"))
      (node (ref "U$8") (pin "IN+") (pinfunction "1_IN+") (pintype "bidirectional"))
    )
    (net (code "34") (name "Net-(U$10-1)") (class "Default")
      (node (ref "R16") (pin "2") (pinfunction "2_2") (pintype "passive"))
      (node (ref "U$10") (pin "IN+") (pinfunction "1_IN+") (pintype "bidirectional"))
    )
    (net (code "35") (name "Net-(U$12-1)") (class "Default")
      (node (ref "R20") (pin "2") (pinfunction "2_2") (pintype "passive"))
      (node (ref "U$12") (pin "IN+") (pinfunction "1_IN+") (pintype "bidirectional"))
    )
    (net (code "36") (name "Net-(X2B-KL)") (class "Default")
      (node (ref "F1") (pin "1") (pinfunction "1_1") (pintype "passive"))
      (node (ref "X2") (pin "2") (pinfunction "KL_2") (pintype "passive"))
    )
    (net (code "37") (name "Net-(X3B-KL)") (class "Default")
      (node (ref "F2") (pin "1") (pinfunction "1_1") (pintype "passive"))
      (node (ref "X3") (pin "2") (pinfunction "KL_2") (pintype "passive"))
    )
    (net (code "38") (name "Net-(X4B-KL)") (class "Default")
      (node (ref "F3") (pin "1") (pinfunction "1_1") (pintype "passive"))
      (node (ref "X4") (pin "2") (pinfunction "KL_2") (pintype "passive"))
    )
    (net (code "39") (name "Net-(X5B-KL)") (class "Default")
      (node (ref "F4") (pin "1") (pinfunction "1_1") (pintype "passive"))
      (node (ref "X5") (pin "2") (pinfunction "KL_2") (pintype "passive"))
    )
    (net (code "40") (name "Net-(X6B-KL)") (class "Default")
      (node (ref "F5") (pin "1") (pinfunction "1_1") (pintype "passive"))
      (node (ref "X6") (pin "2") (pinfunction "KL_2") (pintype "passive"))
    )
    (net (code "41") (name "RELAY1") (class "Default")
      (node (ref "R1") (pin "1") (pinfunction "1_1") (pintype "passive"))
      (node (ref "R2") (pin "2") (pinfunction "2_2") (pintype "passive"))
      (node (ref "U$1") (pin "XIAO_10") (pinfunction "GPIO0_XIAO_10") (pintype "bidirectional"))
    )
    (net (code "42") (name "RELAY2") (class "Default")
      (node (ref "R5") (pin "1") (pinfunction "1_1") (pintype "passive"))
      (node (ref "R6") (pin "2") (pinfunction "2_2") (pintype "passive"))
      (node (ref "U$1") (pin "XIAO_11") (pinfunction "GPIO1_XIAO_11") (pintype "bidirectional"))
    )
    (net (code "43") (name "RELAY3") (class "Default")
      (node (ref "R10") (pin "2") (pinfunction "2_2") (pintype "passive"))
      (node (ref "R9") (pin "1") (pinfunction "1_1") (pintype "passive"))
      (node (ref "U$1") (pin "XIAO_12") (pinfunction "GPIO2_XIAO_12") (pintype "bidirectional"))
    )
    (net (code "44") (name "RELAY4") (class "Default")
      (node (ref "R13") (pin "1") (pinfunction "1_1") (pintype "passive"))
      (node (ref "R14") (pin "2") (pinfunction "2_2") (pintype "passive"))
      (node (ref "U$1") (pin "XIAO_13") (pinfunction "GPIO21_XIAO_13") (pintype "bidirectional"))
    )
    (net (code "45") (name "RELAY5") (class "Default")
      (node (ref "R17") (pin "1") (pinfunction "1_1") (pintype "passive"))
      (node (ref "R18") (pin "2") (pinfunction "2_2") (pintype "passive"))
      (node (ref "U$1") (pin "XIAO_110") (pinfunction "GPIO18_XIAO_110") (pintype "bidirectional"))
    )
    (net (code "46") (name "ROUT1") (class "Default")
      (node (ref "C1") (pin "2") (pinfunction "2_2") (pintype "passive"))
      (node (ref "F1") (pin "2") (pinfunction "2_2") (pintype "passive"))
      (node (ref "U$4") (pin "L2") (pinfunction "4_L2") (pintype "bidirectional"))
    )
    (net (code "47") (name "ROUT2") (class "Default")
      (node (ref "C2") (pin "2") (pinfunction "2_2") (pintype "passive"))
      (node (ref "F2") (pin "2") (pinfunction "2_2") (pintype "passive"))
      (node (ref "U$6") (pin "L2") (pinfunction "4_L2") (pintype "bidirectional"))
    )
    (net (code "48") (name "ROUT3") (class "Default")
      (node (ref "C3") (pin "2") (pinfunction "2_2") (pintype "passive"))
      (node (ref "F3") (pin "2") (pinfunction "2_2") (pintype "passive"))
      (node (ref "U$8") (pin "L2") (pinfunction "4_L2") (pintype "bidirectional"))
    )
    (net (code "49") (name "ROUT4") (class "Default")
      (node (ref "C4") (pin "2") (pinfunction "2_2") (pintype "passive"))
      (node (ref "F4") (pin "2") (pinfunction "2_2") (pintype "passive"))
      (node (ref "U$10") (pin "L2") (pinfunction "4_L2") (pintype "bidirectional"))
    )
    (net (code "50") (name "ROUT5") (class "Default")
      (node (ref "C5") (pin "2") (pinfunction "2_2") (pintype "passive"))
      (node (ref "F5") (pin "2") (pinfunction "2_2") (pintype "passive"))
      (node (ref "U$12") (pin "L2") (pinfunction "4_L2") (pintype "bidirectional"))
    )
    (net (code "51") (name "SENS1") (class "Default")
      (node (ref "R21") (pin "2") (pinfunction "2_2") (pintype "passive"))
      (node (ref "SENSOR1") (pin "P2") (pinfunction "P$2_P2") (pintype "bidirectional"))
      (node (ref "U$1") (pin "XIAO_18") (pinfunction "GPIO19_XIAO_18") (pintype "bidirectional"))
    )
    (net (code "52") (name "SENS2") (class "Default")
      (node (ref "R22") (pin "2") (pinfunction "2_2") (pintype "passive"))
      (node (ref "SENSOR2") (pin "P2") (pinfunction "P$2_P2") (pintype "bidirectional"))
      (node (ref "U$1") (pin "XIAO_19") (pinfunction "GPIO20_XIAO_19") (pintype "bidirectional"))
    )
    (net (code "53") (name "SENS3") (class "Default")
      (node (ref "R23") (pin "2") (pinfunction "2_2") (pintype "passive"))
      (node (ref "SENSOR3") (pin "P2") (pinfunction "P$2_P2") (pintype "bidirectional"))
      (node (ref "U$1") (pin "XIAO_14") (pinfunction "GPIO22_XIAO_14") (pintype "bidirectional"))
    )
    (net (code "54") (name "SENS4") (class "Default")
      (node (ref "R24") (pin "2") (pinfunction "2_2") (pintype "passive"))
      (node (ref "SENSOR4") (pin "P2") (pinfunction "P$2_P2") (pintype "bidirectional"))
      (node (ref "U$1") (pin "XIAO_15") (pinfunction "GPIO23_XIAO_15") (pintype "bidirectional"))
    )
    (net (code "55") (name "unconnected-(SENSOR1-P$3-PadP3)") (class "Default")
      (node (ref "SENSOR1") (pin "P3") (pinfunction "P$3_P3") (pintype "bidirectional"))
    )
    (net (code "56") (name "unconnected-(SENSOR2-P$3-PadP3)") (class "Default")
      (node (ref "SENSOR2") (pin "P3") (pinfunction "P$3_P3") (pintype "bidirectional"))
    )
    (net (code "57") (name "unconnected-(SENSOR3-P$3-PadP3)") (class "Default")
      (node (ref "SENSOR3") (pin "P3") (pinfunction "P$3_P3") (pintype "bidirectional"))
    )
    (net (code "58") (name "unconnected-(SENSOR4-P$3-PadP3)") (class "Default")
      (node (ref "SENSOR4") (pin "P3") (pinfunction "P$3_P3") (pintype "bidirectional"))
    )
    (net (code "59") (name "unconnected-(U$2-NC1-PadP8)") (class "Default")
      (node (ref "U$2") (pin "P8") (pinfunction "NC1_P8") (pintype "bidirectional"))
    )
    (net (code "60") (name "unconnected-(U$2-NC2-PadP9)") (class "Default")
      (node (ref "U$2") (pin "P9") (pinfunction "NC2_P9") (pintype "bidirectional"))
    )
    (net (code "61") (name "unconnected-(U$2-P0_0-PadP23)") (class "Default")
      (node (ref "U$2") (pin "P23") (pinfunction "P0_0_P23") (pintype "bidirectional"))
    )
    (net (code "62") (name "unconnected-(U$2-P0_1-PadP22)") (class "Default")
      (node (ref "U$2") (pin "P22") (pinfunction "P0_1_P22") (pintype "bidirectional"))
    )
    (net (code "63") (name "unconnected-(U$2-P0_4-PadP19)") (class "Default")
      (node (ref "U$2") (pin "P19") (pinfunction "P0_4_P19") (pintype "bidirectional"))
    )
    (net (code "64") (name "unconnected-(U$2-P0_5-PadP18)") (class "Default")
      (node (ref "U$2") (pin "P18") (pinfunction "P0_5_P18") (pintype "bidirectional"))
    )
    (net (code "65") (name "unconnected-(U$2-P0_6-PadP17)") (class "Default")
      (node (ref "U$2") (pin "P17") (pinfunction "P0_6_P17") (pintype "bidirectional"))
    )
    (net (code "66") (name "unconnected-(U$2-P0_7-PadP16)") (class "Default")
      (node (ref "U$2") (pin "P16") (pinfunction "P0_7_P16") (pintype "bidirectional"))
    )
    (net (code "67") (name "unconnected-(U$2-P1_0-PadP15)") (class "Default")
      (node (ref "U$2") (pin "P15") (pinfunction "P1_0_P15") (pintype "bidirectional"))
    )
    (net (code "68") (name "unconnected-(U$2-P1_1-PadP14)") (class "Default")
      (node (ref "U$2") (pin "P14") (pinfunction "P1_1_P14") (pintype "bidirectional"))
    )
    (net (code "69") (name "unconnected-(U$2-P1_2-PadP13)") (class "Default")
      (node (ref "U$2") (pin "P13") (pinfunction "P1_2_P13") (pintype "bidirectional"))
    )
    (net (code "70") (name "unconnected-(U$2-P1_3-PadP12)") (class "Default")
      (node (ref "U$2") (pin "P12") (pinfunction "P1_3_P12") (pintype "bidirectional"))
    )
    (net (code "71") (name "unconnected-(U$2-P1_4-PadP11)") (class "Default")
      (node (ref "U$2") (pin "P11") (pinfunction "P1_4_P11") (pintype "bidirectional"))
    )
    (net (code "72") (name "unconnected-(U$2-P1_5-PadP10)") (class "Default")
      (node (ref "U$2") (pin "P10") (pinfunction "P1_5_P10") (pintype "bidirectional"))
    )
    (net (code "73") (name "unconnected-(U$2-P1_6-PadP7)") (class "Default")
      (node (ref "U$2") (pin "P7") (pinfunction "P1_6_P7") (pintype "bidirectional"))
    )
    (net (code "74") (name "unconnected-(U$2-P1_7-PadP6)") (class "Default")
      (node (ref "U$2") (pin "P6") (pinfunction "P1_7_P6") (pintype "bidirectional"))
    )
    (net (code "75") (name "unconnected-(U$2-P2_0-PadP5)") (class "Default")
      (node (ref "U$2") (pin "P5") (pinfunction "P2_0_P5") (pintype "bidirectional"))
    )
  )
)
